# Mega_Base_Shield.net
KiCad netlist of a schematic drawn in EAGLE
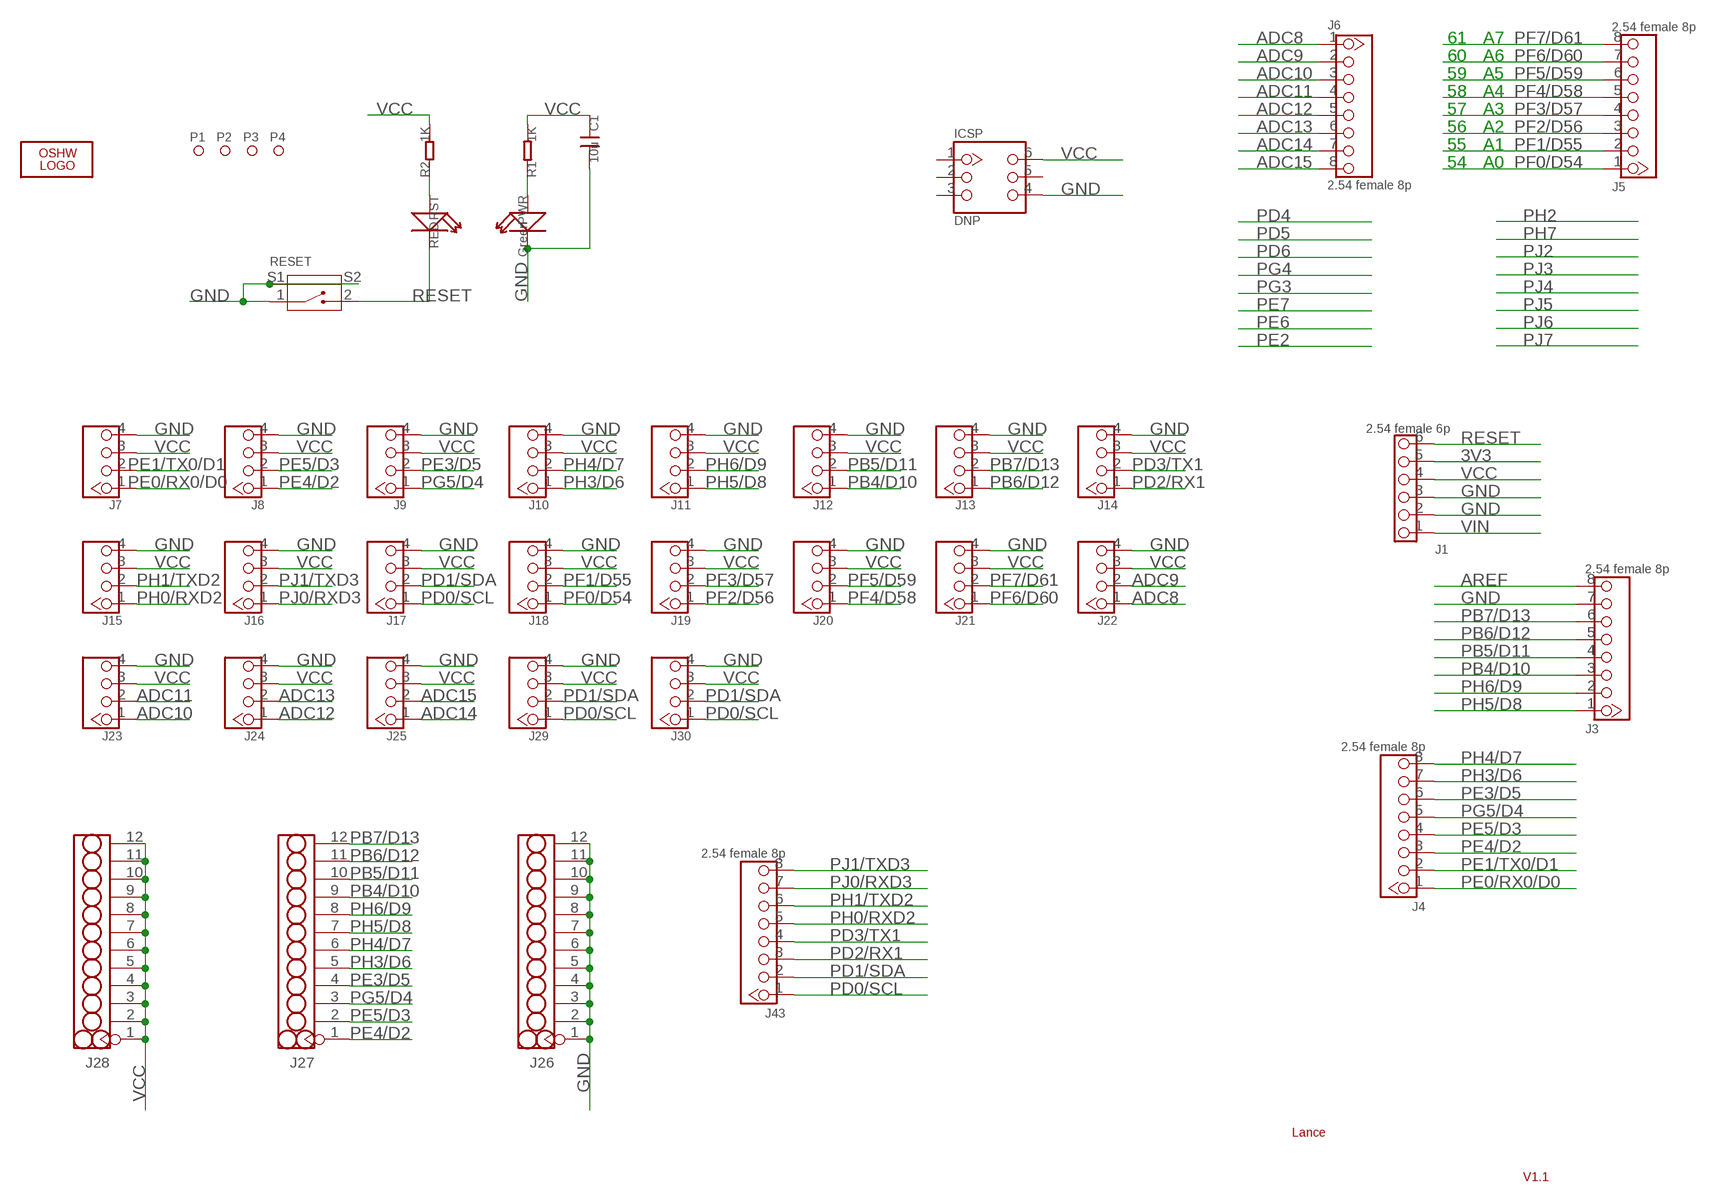
[diagram p0: schematic, sheet 1]

(export (version "E")
  (design (tool "Eeschema 10.0.6"))
  (components
    (comp (ref "C1")
      (value "10u")
      (footprint "eagle-import:0805")
      (libsource (lib "eagle-import") (part "C-0805"))
    )
    (comp (ref "ICSP")
      (value "DNP")
      (footprint "eagle-import:2X3P-2.54-LEADED-60_35")
      (libsource (lib "eagle-import") (part "HEADER-2X3P'60/35'"))
    )
    (comp (ref "J1")
      (value "2.54 female 6p")
      (footprint "eagle-import:6P-2.54-LEADED")
      (libsource (lib "eagle-import") (part "HEADER-6P-LEADED-2.54"))
    )
    (comp (ref "J3")
      (value "2.54 female 8p")
      (footprint "eagle-import:8P-2.54-LEADED")
      (libsource (lib "eagle-import") (part "HEADER-8P-2.54-LEADED"))
    )
    (comp (ref "J4")
      (value "2.54 female 8p")
      (footprint "eagle-import:8P-2.54-LEADED")
      (libsource (lib "eagle-import") (part "HEADER-8P-2.54-LEADED"))
    )
    (comp (ref "J5")
      (value "2.54 female 8p")
      (footprint "eagle-import:8P-2.54-LEADED")
      (libsource (lib "eagle-import") (part "HEADER-8P-2.54-LEADED"))
    )
    (comp (ref "J6")
      (value "2.54 female 8p")
      (footprint "eagle-import:8P-2.54-LEADED")
      (libsource (lib "eagle-import") (part "HEADER-8P-2.54-LEADED"))
    )
    (comp (ref "J7")
      (value "TWIG-2.0-LEADED'90D'")
      (footprint "eagle-import:4P-LEADED-2.0-90")
      (libsource (lib "eagle-import") (part "TWIG-2.0-LEADED'90D'"))
    )
    (comp (ref "J8")
      (value "TWIG-2.0-LEADED")
      (footprint "eagle-import:4P-LEADED-2.0")
      (libsource (lib "eagle-import") (part "TWIG-2.0-LEADED"))
    )
    (comp (ref "J9")
      (value "TWIG-2.0-LEADED")
      (footprint "eagle-import:4P-LEADED-2.0")
      (libsource (lib "eagle-import") (part "TWIG-2.0-LEADED"))
    )
    (comp (ref "J10")
      (value "TWIG-2.0-LEADED")
      (footprint "eagle-import:4P-LEADED-2.0")
      (libsource (lib "eagle-import") (part "TWIG-2.0-LEADED"))
    )
    (comp (ref "J11")
      (value "TWIG-2.0-LEADED")
      (footprint "eagle-import:4P-LEADED-2.0")
      (libsource (lib "eagle-import") (part "TWIG-2.0-LEADED"))
    )
    (comp (ref "J12")
      (value "TWIG-2.0-LEADED")
      (footprint "eagle-import:4P-LEADED-2.0")
      (libsource (lib "eagle-import") (part "TWIG-2.0-LEADED"))
    )
    (comp (ref "J13")
      (value "TWIG-2.0-LEADED")
      (footprint "eagle-import:4P-LEADED-2.0")
      (libsource (lib "eagle-import") (part "TWIG-2.0-LEADED"))
    )
    (comp (ref "J14")
      (value "TWIG-2.0-LEADED'90D'")
      (footprint "eagle-import:4P-LEADED-2.0-90")
      (libsource (lib "eagle-import") (part "TWIG-2.0-LEADED'90D'"))
    )
    (comp (ref "J15")
      (value "TWIG-2.0-LEADED'90D'")
      (footprint "eagle-import:4P-LEADED-2.0-90")
      (libsource (lib "eagle-import") (part "TWIG-2.0-LEADED'90D'"))
    )
    (comp (ref "J16")
      (value "TWIG-2.0-LEADED'90D'")
      (footprint "eagle-import:4P-LEADED-2.0-90")
      (libsource (lib "eagle-import") (part "TWIG-2.0-LEADED'90D'"))
    )
    (comp (ref "J17")
      (value "TWIG-2.0-LEADED'90D'")
      (footprint "eagle-import:4P-LEADED-2.0-90")
      (libsource (lib "eagle-import") (part "TWIG-2.0-LEADED'90D'"))
    )
    (comp (ref "J18")
      (value "TWIG-2.0-LEADED")
      (footprint "eagle-import:4P-LEADED-2.0")
      (libsource (lib "eagle-import") (part "TWIG-2.0-LEADED"))
    )
    (comp (ref "J19")
      (value "TWIG-2.0-LEADED")
      (footprint "eagle-import:4P-LEADED-2.0")
      (libsource (lib "eagle-import") (part "TWIG-2.0-LEADED"))
    )
    (comp (ref "J20")
      (value "TWIG-2.0-LEADED")
      (footprint "eagle-import:4P-LEADED-2.0")
      (libsource (lib "eagle-import") (part "TWIG-2.0-LEADED"))
    )
    (comp (ref "J21")
      (value "TWIG-2.0-LEADED")
      (footprint "eagle-import:4P-LEADED-2.0")
      (libsource (lib "eagle-import") (part "TWIG-2.0-LEADED"))
    )
    (comp (ref "J22")
      (value "TWIG-2.0-LEADED")
      (footprint "eagle-import:4P-LEADED-2.0")
      (libsource (lib "eagle-import") (part "TWIG-2.0-LEADED"))
    )
    (comp (ref "J23")
      (value "TWIG-2.0-LEADED")
      (footprint "eagle-import:4P-LEADED-2.0")
      (libsource (lib "eagle-import") (part "TWIG-2.0-LEADED"))
    )
    (comp (ref "J24")
      (value "TWIG-2.0-LEADED")
      (footprint "eagle-import:4P-LEADED-2.0")
      (libsource (lib "eagle-import") (part "TWIG-2.0-LEADED"))
    )
    (comp (ref "J25")
      (value "TWIG-2.0-LEADED")
      (footprint "eagle-import:4P-LEADED-2.0")
      (libsource (lib "eagle-import") (part "TWIG-2.0-LEADED"))
    )
    (comp (ref "J26")
      (value "HEADER-12P-2.54")
      (footprint "eagle-import:12P-2.54-LEADED")
      (libsource (lib "eagle-import") (part "HEADER-12P-2.54"))
    )
    (comp (ref "J27")
      (value "HEADER-12P-2.54")
      (footprint "eagle-import:12P-2.54-LEADED")
      (libsource (lib "eagle-import") (part "HEADER-12P-2.54"))
    )
    (comp (ref "J28")
      (value "HEADER-12P-2.54")
      (footprint "eagle-import:12P-2.54-LEADED")
      (libsource (lib "eagle-import") (part "HEADER-12P-2.54"))
    )
    (comp (ref "J29")
      (value "TWIG-2.0-LEADED")
      (footprint "eagle-import:4P-LEADED-2.0")
      (libsource (lib "eagle-import") (part "TWIG-2.0-LEADED"))
    )
    (comp (ref "J30")
      (value "TWIG-2.0-LEADED")
      (footprint "eagle-import:4P-LEADED-2.0")
      (libsource (lib "eagle-import") (part "TWIG-2.0-LEADED"))
    )
    (comp (ref "J43")
      (value "2.54 female 8p")
      (footprint "eagle-import:8P-2.54-LEADED")
      (libsource (lib "eagle-import") (part "HEADER-8P-2.54-LEADED"))
    )
    (comp (ref "LOGO1")
      (value "LOGO-OSHW-FILLX0200-NT")
      (footprint "eagle-import:OSHW_FILLX200_NOTEXT")
      (libsource (lib "eagle-import") (part "LOGO-OSHW-FILLX0200-NT"))
    )
    (comp (ref "P1")
      (value "PAD-MARK'ANNULAR'")
      (footprint "eagle-import:ROUND-MARK-1.0")
      (fields (field (name "PARTNO") "DNP"))
      (libsource (lib "eagle-import") (part "PAD-MARK'ANNULAR'"))
    )
    (comp (ref "P2")
      (value "PAD-MARK'ANNULAR'")
      (footprint "eagle-import:ROUND-MARK-1.0")
      (fields (field (name "PARTNO") "DNP"))
      (libsource (lib "eagle-import") (part "PAD-MARK'ANNULAR'"))
    )
    (comp (ref "P3")
      (value "PAD-MARK'ANNULAR'")
      (footprint "eagle-import:ROUND-MARK-1.0")
      (fields (field (name "PARTNO") "DNP"))
      (libsource (lib "eagle-import") (part "PAD-MARK'ANNULAR'"))
    )
    (comp (ref "P4")
      (value "PAD-MARK'ANNULAR'")
      (footprint "eagle-import:ROUND-MARK-1.0")
      (fields (field (name "PARTNO") "DNP"))
      (libsource (lib "eagle-import") (part "PAD-MARK'ANNULAR'"))
    )
    (comp (ref "PWR")
      (value "Green")
      (footprint "eagle-import:D0603")
      (libsource (lib "eagle-import") (part "LED-0603"))
    )
    (comp (ref "R1")
      (value "1K")
      (footprint "eagle-import:0402")
      (libsource (lib "eagle-import") (part "R-0402"))
    )
    (comp (ref "R2")
      (value "1K")
      (footprint "eagle-import:0402")
      (libsource (lib "eagle-import") (part "R-0402"))
    )
    (comp (ref "RESET")
      (value "BUTTON-2+2P'TS-1188E'")
      (footprint "eagle-import:4P-SMD-L7.0_W3.5_H3.5MM-90D")
      (libsource (lib "eagle-import") (part "BUTTON-2+2P'TS-1188E'"))
    )
    (comp (ref "RST")
      (value "RED")
      (footprint "eagle-import:D0603")
      (libsource (lib "eagle-import") (part "LED-0603"))
    )
  )
  (nets
    (net (code "1") (name "/3V3") (class "Default")
      (node (ref "J1") (pin "5") (pinfunction "5_5") (pintype "bidirectional"))
    )
    (net (code "2") (name "/ADC8") (class "Default")
      (node (ref "J22") (pin "1") (pinfunction "1_1") (pintype "bidirectional"))
      (node (ref "J6") (pin "1") (pinfunction "1_1") (pintype "bidirectional"))
    )
    (net (code "3") (name "/ADC9") (class "Default")
      (node (ref "J22") (pin "2") (pinfunction "2_2") (pintype "bidirectional"))
      (node (ref "J6") (pin "2") (pinfunction "2_2") (pintype "bidirectional"))
    )
    (net (code "4") (name "/ADC10") (class "Default")
      (node (ref "J23") (pin "1") (pinfunction "1_1") (pintype "bidirectional"))
      (node (ref "J6") (pin "3") (pinfunction "3_3") (pintype "bidirectional"))
    )
    (net (code "5") (name "/ADC11") (class "Default")
      (node (ref "J23") (pin "2") (pinfunction "2_2") (pintype "bidirectional"))
      (node (ref "J6") (pin "4") (pinfunction "4_4") (pintype "bidirectional"))
    )
    (net (code "6") (name "/ADC12") (class "Default")
      (node (ref "J24") (pin "1") (pinfunction "1_1") (pintype "bidirectional"))
      (node (ref "J6") (pin "5") (pinfunction "5_5") (pintype "bidirectional"))
    )
    (net (code "7") (name "/ADC13") (class "Default")
      (node (ref "J24") (pin "2") (pinfunction "2_2") (pintype "bidirectional"))
      (node (ref "J6") (pin "6") (pinfunction "6_6") (pintype "bidirectional"))
    )
    (net (code "8") (name "/ADC14") (class "Default")
      (node (ref "J25") (pin "1") (pinfunction "1_1") (pintype "bidirectional"))
      (node (ref "J6") (pin "7") (pinfunction "7_7") (pintype "bidirectional"))
    )
    (net (code "9") (name "/ADC15") (class "Default")
      (node (ref "J25") (pin "2") (pinfunction "2_2") (pintype "bidirectional"))
      (node (ref "J6") (pin "8") (pinfunction "8_8") (pintype "bidirectional"))
    )
    (net (code "10") (name "/AREF") (class "Default")
      (node (ref "J3") (pin "8") (pinfunction "8_8") (pintype "bidirectional"))
    )
    (net (code "11") (name "/GND") (class "Default")
      (node (ref "C1") (pin "2") (pinfunction "2_2") (pintype "passive"))
      (node (ref "ICSP") (pin "4") (pinfunction "4_4") (pintype "bidirectional"))
      (node (ref "J1") (pin "2") (pinfunction "2_2") (pintype "bidirectional"))
      (node (ref "J1") (pin "3") (pinfunction "3_3") (pintype "bidirectional"))
      (node (ref "J10") (pin "4") (pinfunction "4_4") (pintype "bidirectional"))
      (node (ref "J11") (pin "4") (pinfunction "4_4") (pintype "bidirectional"))
      (node (ref "J12") (pin "4") (pinfunction "4_4") (pintype "bidirectional"))
      (node (ref "J13") (pin "4") (pinfunction "4_4") (pintype "bidirectional"))
      (node (ref "J14") (pin "4") (pinfunction "4_4") (pintype "bidirectional"))
      (node (ref "J15") (pin "4") (pinfunction "4_4") (pintype "bidirectional"))
      (node (ref "J16") (pin "4") (pinfunction "4_4") (pintype "bidirectional"))
      (node (ref "J17") (pin "4") (pinfunction "4_4") (pintype "bidirectional"))
      (node (ref "J18") (pin "4") (pinfunction "4_4") (pintype "bidirectional"))
      (node (ref "J19") (pin "4") (pinfunction "4_4") (pintype "bidirectional"))
      (node (ref "J20") (pin "4") (pinfunction "4_4") (pintype "bidirectional"))
      (node (ref "J21") (pin "4") (pinfunction "4_4") (pintype "bidirectional"))
      (node (ref "J22") (pin "4") (pinfunction "4_4") (pintype "bidirectional"))
      (node (ref "J23") (pin "4") (pinfunction "4_4") (pintype "bidirectional"))
      (node (ref "J24") (pin "4") (pinfunction "4_4") (pintype "bidirectional"))
      (node (ref "J25") (pin "4") (pinfunction "4_4") (pintype "bidirectional"))
      (node (ref "J26") (pin "1") (pinfunction "1_1") (pintype "bidirectional"))
      (node (ref "J26") (pin "10") (pinfunction "10_10") (pintype "bidirectional"))
      (node (ref "J26") (pin "11") (pinfunction "11_11") (pintype "bidirectional"))
      (node (ref "J26") (pin "12") (pinfunction "12_12") (pintype "bidirectional"))
      (node (ref "J26") (pin "2") (pinfunction "2_2") (pintype "bidirectional"))
      (node (ref "J26") (pin "3") (pinfunction "3_3") (pintype "bidirectional"))
      (node (ref "J26") (pin "4") (pinfunction "4_4") (pintype "bidirectional"))
      (node (ref "J26") (pin "5") (pinfunction "5_5") (pintype "bidirectional"))
      (node (ref "J26") (pin "6") (pinfunction "6_6") (pintype "bidirectional"))
      (node (ref "J26") (pin "7") (pinfunction "7_7") (pintype "bidirectional"))
      (node (ref "J26") (pin "8") (pinfunction "8_8") (pintype "bidirectional"))
      (node (ref "J26") (pin "9") (pinfunction "9_9") (pintype "bidirectional"))
      (node (ref "J29") (pin "4") (pinfunction "4_4") (pintype "bidirectional"))
      (node (ref "J3") (pin "7") (pinfunction "7_7") (pintype "bidirectional"))
      (node (ref "J30") (pin "4") (pinfunction "4_4") (pintype "bidirectional"))
      (node (ref "J7") (pin "4") (pinfunction "4_4") (pintype "bidirectional"))
      (node (ref "J8") (pin "4") (pinfunction "4_4") (pintype "bidirectional"))
      (node (ref "J9") (pin "4") (pinfunction "4_4") (pintype "bidirectional"))
      (node (ref "PWR") (pin "-") (pinfunction "-_-") (pintype "passive"))
      (node (ref "RESET") (pin "1") (pinfunction "1_1") (pintype "bidirectional"))
      (node (ref "RESET") (pin "S1") (pinfunction "S1_S1") (pintype "bidirectional"))
      (node (ref "RESET") (pin "S2") (pinfunction "S2_S2") (pintype "bidirectional"))
    )
    (net (code "12") (name "/PB4{slash}D10") (class "Default")
      (node (ref "J12") (pin "1") (pinfunction "1_1") (pintype "bidirectional"))
      (node (ref "J27") (pin "9") (pinfunction "9_9") (pintype "bidirectional"))
      (node (ref "J3") (pin "3") (pinfunction "3_3") (pintype "bidirectional"))
    )
    (net (code "13") (name "/PB5{slash}D11") (class "Default")
      (node (ref "J12") (pin "2") (pinfunction "2_2") (pintype "bidirectional"))
      (node (ref "J27") (pin "10") (pinfunction "10_10") (pintype "bidirectional"))
      (node (ref "J3") (pin "4") (pinfunction "4_4") (pintype "bidirectional"))
    )
    (net (code "14") (name "/PB6{slash}D12") (class "Default")
      (node (ref "J13") (pin "1") (pinfunction "1_1") (pintype "bidirectional"))
      (node (ref "J27") (pin "11") (pinfunction "11_11") (pintype "bidirectional"))
      (node (ref "J3") (pin "5") (pinfunction "5_5") (pintype "bidirectional"))
    )
    (net (code "15") (name "/PB7{slash}D13") (class "Default")
      (node (ref "J13") (pin "2") (pinfunction "2_2") (pintype "bidirectional"))
      (node (ref "J27") (pin "12") (pinfunction "12_12") (pintype "bidirectional"))
      (node (ref "J3") (pin "6") (pinfunction "6_6") (pintype "bidirectional"))
    )
    (net (code "16") (name "/PD0{slash}SCL") (class "Default")
      (node (ref "J17") (pin "1") (pinfunction "1_1") (pintype "bidirectional"))
      (node (ref "J29") (pin "1") (pinfunction "1_1") (pintype "bidirectional"))
      (node (ref "J30") (pin "1") (pinfunction "1_1") (pintype "bidirectional"))
      (node (ref "J43") (pin "1") (pinfunction "1_1") (pintype "bidirectional"))
    )
    (net (code "17") (name "/PD1{slash}SDA") (class "Default")
      (node (ref "J17") (pin "2") (pinfunction "2_2") (pintype "bidirectional"))
      (node (ref "J29") (pin "2") (pinfunction "2_2") (pintype "bidirectional"))
      (node (ref "J30") (pin "2") (pinfunction "2_2") (pintype "bidirectional"))
      (node (ref "J43") (pin "2") (pinfunction "2_2") (pintype "bidirectional"))
    )
    (net (code "18") (name "/PD2{slash}RX1") (class "Default")
      (node (ref "J14") (pin "1") (pinfunction "1_1") (pintype "bidirectional"))
      (node (ref "J43") (pin "3") (pinfunction "3_3") (pintype "bidirectional"))
    )
    (net (code "19") (name "/PD3{slash}TX1") (class "Default")
      (node (ref "J14") (pin "2") (pinfunction "2_2") (pintype "bidirectional"))
      (node (ref "J43") (pin "4") (pinfunction "4_4") (pintype "bidirectional"))
    )
    (net (code "23") (name "/PE0{slash}RX0{slash}D0") (class "Default")
      (node (ref "J4") (pin "1") (pinfunction "1_1") (pintype "bidirectional"))
      (node (ref "J7") (pin "1") (pinfunction "1_1") (pintype "bidirectional"))
    )
    (net (code "24") (name "/PE1{slash}TX0{slash}D1") (class "Default")
      (node (ref "J4") (pin "2") (pinfunction "2_2") (pintype "bidirectional"))
      (node (ref "J7") (pin "2") (pinfunction "2_2") (pintype "bidirectional"))
    )
    (net (code "26") (name "/PE3{slash}D5") (class "Default")
      (node (ref "J27") (pin "4") (pinfunction "4_4") (pintype "bidirectional"))
      (node (ref "J4") (pin "6") (pinfunction "6_6") (pintype "bidirectional"))
      (node (ref "J9") (pin "2") (pinfunction "2_2") (pintype "bidirectional"))
    )
    (net (code "27") (name "/PE4{slash}D2") (class "Default")
      (node (ref "J27") (pin "1") (pinfunction "1_1") (pintype "bidirectional"))
      (node (ref "J4") (pin "3") (pinfunction "3_3") (pintype "bidirectional"))
      (node (ref "J8") (pin "1") (pinfunction "1_1") (pintype "bidirectional"))
    )
    (net (code "28") (name "/PE5{slash}D3") (class "Default")
      (node (ref "J27") (pin "2") (pinfunction "2_2") (pintype "bidirectional"))
      (node (ref "J4") (pin "4") (pinfunction "4_4") (pintype "bidirectional"))
      (node (ref "J8") (pin "2") (pinfunction "2_2") (pintype "bidirectional"))
    )
    (net (code "31") (name "/PF0{slash}D54") (class "Default")
      (node (ref "J18") (pin "1") (pinfunction "1_1") (pintype "bidirectional"))
      (node (ref "J5") (pin "1") (pinfunction "1_1") (pintype "bidirectional"))
    )
    (net (code "32") (name "/PF1{slash}D55") (class "Default")
      (node (ref "J18") (pin "2") (pinfunction "2_2") (pintype "bidirectional"))
      (node (ref "J5") (pin "2") (pinfunction "2_2") (pintype "bidirectional"))
    )
    (net (code "33") (name "/PF2{slash}D56") (class "Default")
      (node (ref "J19") (pin "1") (pinfunction "1_1") (pintype "bidirectional"))
      (node (ref "J5") (pin "3") (pinfunction "3_3") (pintype "bidirectional"))
    )
    (net (code "34") (name "/PF3{slash}D57") (class "Default")
      (node (ref "J19") (pin "2") (pinfunction "2_2") (pintype "bidirectional"))
      (node (ref "J5") (pin "4") (pinfunction "4_4") (pintype "bidirectional"))
    )
    (net (code "35") (name "/PF4{slash}D58") (class "Default")
      (node (ref "J20") (pin "1") (pinfunction "1_1") (pintype "bidirectional"))
      (node (ref "J5") (pin "5") (pinfunction "5_5") (pintype "bidirectional"))
    )
    (net (code "36") (name "/PF5{slash}D59") (class "Default")
      (node (ref "J20") (pin "2") (pinfunction "2_2") (pintype "bidirectional"))
      (node (ref "J5") (pin "6") (pinfunction "6_6") (pintype "bidirectional"))
    )
    (net (code "37") (name "/PF6{slash}D60") (class "Default")
      (node (ref "J21") (pin "1") (pinfunction "1_1") (pintype "bidirectional"))
      (node (ref "J5") (pin "7") (pinfunction "7_7") (pintype "bidirectional"))
    )
    (net (code "38") (name "/PF7{slash}D61") (class "Default")
      (node (ref "J21") (pin "2") (pinfunction "2_2") (pintype "bidirectional"))
      (node (ref "J5") (pin "8") (pinfunction "8_8") (pintype "bidirectional"))
    )
    (net (code "41") (name "/PG5{slash}D4") (class "Default")
      (node (ref "J27") (pin "3") (pinfunction "3_3") (pintype "bidirectional"))
      (node (ref "J4") (pin "5") (pinfunction "5_5") (pintype "bidirectional"))
      (node (ref "J9") (pin "1") (pinfunction "1_1") (pintype "bidirectional"))
    )
    (net (code "42") (name "/PH0{slash}RXD2") (class "Default")
      (node (ref "J15") (pin "1") (pinfunction "1_1") (pintype "bidirectional"))
      (node (ref "J43") (pin "5") (pinfunction "5_5") (pintype "bidirectional"))
    )
    (net (code "43") (name "/PH1{slash}TXD2") (class "Default")
      (node (ref "J15") (pin "2") (pinfunction "2_2") (pintype "bidirectional"))
      (node (ref "J43") (pin "6") (pinfunction "6_6") (pintype "bidirectional"))
    )
    (net (code "45") (name "/PH3{slash}D6") (class "Default")
      (node (ref "J10") (pin "1") (pinfunction "1_1") (pintype "bidirectional"))
      (node (ref "J27") (pin "5") (pinfunction "5_5") (pintype "bidirectional"))
      (node (ref "J4") (pin "7") (pinfunction "7_7") (pintype "bidirectional"))
    )
    (net (code "46") (name "/PH4{slash}D7") (class "Default")
      (node (ref "J10") (pin "2") (pinfunction "2_2") (pintype "bidirectional"))
      (node (ref "J27") (pin "6") (pinfunction "6_6") (pintype "bidirectional"))
      (node (ref "J4") (pin "8") (pinfunction "8_8") (pintype "bidirectional"))
    )
    (net (code "47") (name "/PH5{slash}D8") (class "Default")
      (node (ref "J11") (pin "1") (pinfunction "1_1") (pintype "bidirectional"))
      (node (ref "J27") (pin "7") (pinfunction "7_7") (pintype "bidirectional"))
      (node (ref "J3") (pin "1") (pinfunction "1_1") (pintype "bidirectional"))
    )
    (net (code "48") (name "/PH6{slash}D9") (class "Default")
      (node (ref "J11") (pin "2") (pinfunction "2_2") (pintype "bidirectional"))
      (node (ref "J27") (pin "8") (pinfunction "8_8") (pintype "bidirectional"))
      (node (ref "J3") (pin "2") (pinfunction "2_2") (pintype "bidirectional"))
    )
    (net (code "50") (name "/PJ0{slash}RXD3") (class "Default")
      (node (ref "J16") (pin "1") (pinfunction "1_1") (pintype "bidirectional"))
      (node (ref "J43") (pin "7") (pinfunction "7_7") (pintype "bidirectional"))
    )
    (net (code "51") (name "/PJ1{slash}TXD3") (class "Default")
      (node (ref "J16") (pin "2") (pinfunction "2_2") (pintype "bidirectional"))
      (node (ref "J43") (pin "8") (pinfunction "8_8") (pintype "bidirectional"))
    )
    (net (code "58") (name "/RESET") (class "Default")
      (node (ref "J1") (pin "6") (pinfunction "6_6") (pintype "bidirectional"))
      (node (ref "RESET") (pin "2") (pinfunction "2_2") (pintype "bidirectional"))
      (node (ref "RST") (pin "-") (pinfunction "-_-") (pintype "passive"))
    )
    (net (code "59") (name "/VCC") (class "Default")
      (node (ref "C1") (pin "1") (pinfunction "1_1") (pintype "passive"))
      (node (ref "ICSP") (pin "6") (pinfunction "6_6") (pintype "bidirectional"))
      (node (ref "J1") (pin "4") (pinfunction "4_4") (pintype "bidirectional"))
      (node (ref "J10") (pin "3") (pinfunction "3_3") (pintype "bidirectional"))
      (node (ref "J11") (pin "3") (pinfunction "3_3") (pintype "bidirectional"))
      (node (ref "J12") (pin "3") (pinfunction "3_3") (pintype "bidirectional"))
      (node (ref "J13") (pin "3") (pinfunction "3_3") (pintype "bidirectional"))
      (node (ref "J14") (pin "3") (pinfunction "3_3") (pintype "bidirectional"))
      (node (ref "J15") (pin "3") (pinfunction "3_3") (pintype "bidirectional"))
      (node (ref "J16") (pin "3") (pinfunction "3_3") (pintype "bidirectional"))
      (node (ref "J17") (pin "3") (pinfunction "3_3") (pintype "bidirectional"))
      (node (ref "J18") (pin "3") (pinfunction "3_3") (pintype "bidirectional"))
      (node (ref "J19") (pin "3") (pinfunction "3_3") (pintype "bidirectional"))
      (node (ref "J20") (pin "3") (pinfunction "3_3") (pintype "bidirectional"))
      (node (ref "J21") (pin "3") (pinfunction "3_3") (pintype "bidirectional"))
      (node (ref "J22") (pin "3") (pinfunction "3_3") (pintype "bidirectional"))
      (node (ref "J23") (pin "3") (pinfunction "3_3") (pintype "bidirectional"))
      (node (ref "J24") (pin "3") (pinfunction "3_3") (pintype "bidirectional"))
      (node (ref "J25") (pin "3") (pinfunction "3_3") (pintype "bidirectional"))
      (node (ref "J28") (pin "1") (pinfunction "1_1") (pintype "bidirectional"))
      (node (ref "J28") (pin "10") (pinfunction "10_10") (pintype "bidirectional"))
      (node (ref "J28") (pin "11") (pinfunction "11_11") (pintype "bidirectional"))
      (node (ref "J28") (pin "12") (pinfunction "12_12") (pintype "bidirectional"))
      (node (ref "J28") (pin "2") (pinfunction "2_2") (pintype "bidirectional"))
      (node (ref "J28") (pin "3") (pinfunction "3_3") (pintype "bidirectional"))
      (node (ref "J28") (pin "4") (pinfunction "4_4") (pintype "bidirectional"))
      (node (ref "J28") (pin "5") (pinfunction "5_5") (pintype "bidirectional"))
      (node (ref "J28") (pin "6") (pinfunction "6_6") (pintype "bidirectional"))
      (node (ref "J28") (pin "7") (pinfunction "7_7") (pintype "bidirectional"))
      (node (ref "J28") (pin "8") (pinfunction "8_8") (pintype "bidirectional"))
      (node (ref "J28") (pin "9") (pinfunction "9_9") (pintype "bidirectional"))
      (node (ref "J29") (pin "3") (pinfunction "3_3") (pintype "bidirectional"))
      (node (ref "J30") (pin "3") (pinfunction "3_3") (pintype "bidirectional"))
      (node (ref "J7") (pin "3") (pinfunction "3_3") (pintype "bidirectional"))
      (node (ref "J8") (pin "3") (pinfunction "3_3") (pintype "bidirectional"))
      (node (ref "J9") (pin "3") (pinfunction "3_3") (pintype "bidirectional"))
      (node (ref "R1") (pin "2") (pinfunction "2_2") (pintype "passive"))
      (node (ref "R2") (pin "2") (pinfunction "2_2") (pintype "passive"))
    )
    (net (code "60") (name "/VIN") (class "Default")
      (node (ref "J1") (pin "1") (pinfunction "1_1") (pintype "bidirectional"))
    )
    (net (code "61") (name "Net-(PWR-Pad+)") (class "Default")
      (node (ref "PWR") (pin "+") (pinfunction "+_+") (pintype "passive"))
      (node (ref "R1") (pin "1") (pinfunction "1_1") (pintype "passive"))
    )
    (net (code "62") (name "Net-(R2-Pad1)") (class "Default")
      (node (ref "R2") (pin "1") (pinfunction "1_1") (pintype "passive"))
      (node (ref "RST") (pin "+") (pinfunction "+_+") (pintype "passive"))
    )
    (net (code "63") (name "unconnected-(ICSP-Pad1)") (class "Default")
      (node (ref "ICSP") (pin "1") (pinfunction "1_1") (pintype "bidirectional"))
    )
    (net (code "64") (name "unconnected-(ICSP-Pad2)") (class "Default")
      (node (ref "ICSP") (pin "2") (pinfunction "2_2") (pintype "bidirectional"))
    )
    (net (code "65") (name "unconnected-(ICSP-Pad3)") (class "Default")
      (node (ref "ICSP") (pin "3") (pinfunction "3_3") (pintype "bidirectional"))
    )
    (net (code "66") (name "unconnected-(ICSP-Pad5)") (class "Default")
      (node (ref "ICSP") (pin "5") (pinfunction "5_5") (pintype "bidirectional"))
    )
  )
)
